# LED-Board.net
KiCad netlist of a schematic drawn in EAGLE
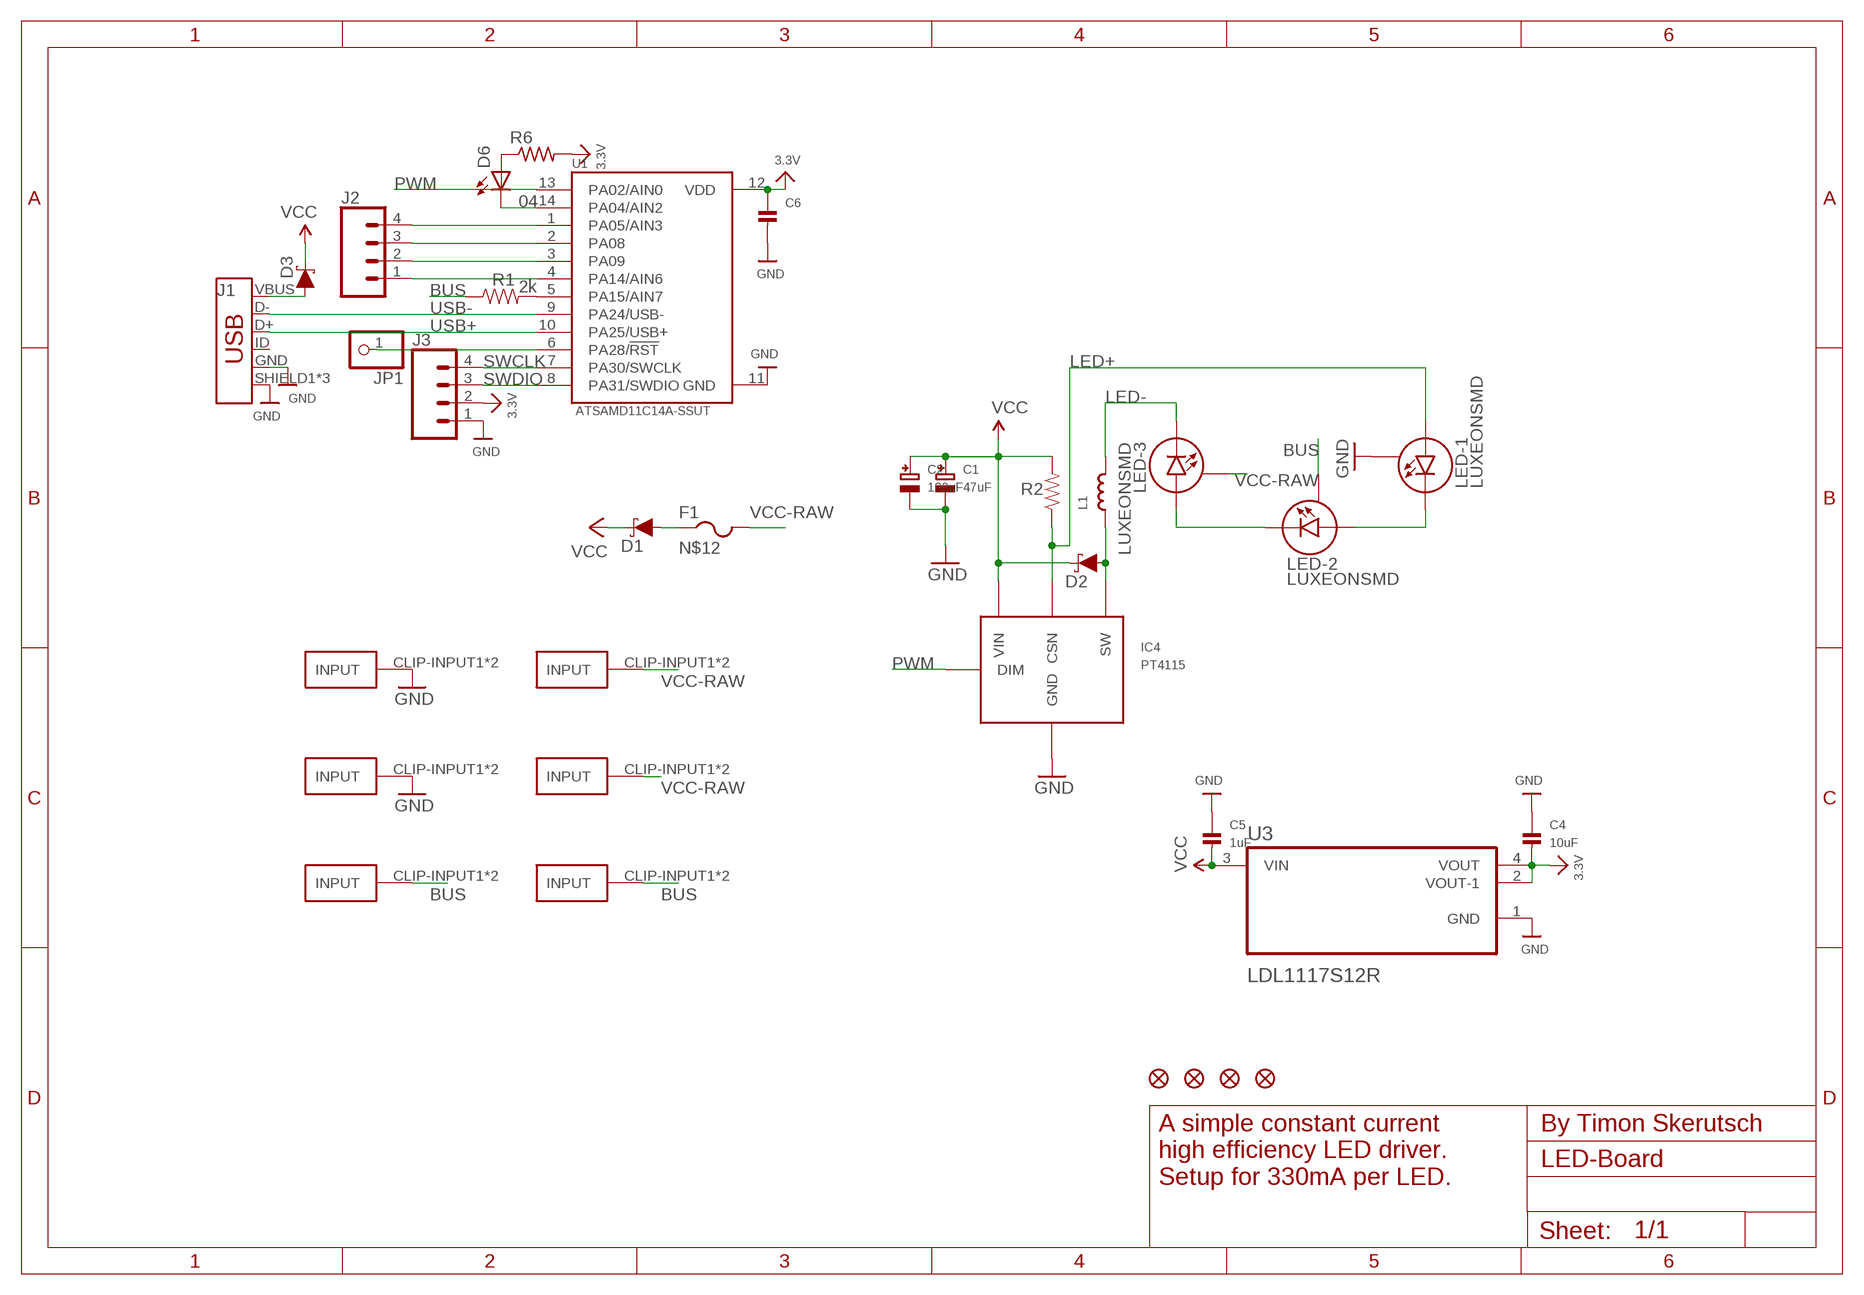
[diagram p0: schematic, sheet 1]

(export (version "E")
  (design (tool "Eeschema 10.0.6"))
  (components
    (comp (ref "C1")
      (value "47uF")
      (footprint "eagle-import:PANASONIC_C")
      (libsource (lib "eagle-import") (part "CAP_ELECTROLYTICPANASONIC_C"))
    )
    (comp (ref "C2")
      (value "100uF")
      (footprint "eagle-import:PANASONIC_C")
      (libsource (lib "eagle-import") (part "CAP_ELECTROLYTICPANASONIC_C"))
    )
    (comp (ref "C4")
      (value "10uF")
      (footprint "eagle-import:0805")
      (libsource (lib "eagle-import") (part "CAP_CERAMIC0805"))
    )
    (comp (ref "C5")
      (value "1uF")
      (footprint "eagle-import:0603")
      (libsource (lib "eagle-import") (part "CAP_CERAMIC0603"))
    )
    (comp (ref "C6")
      (value "CAP_CERAMIC0603")
      (footprint "eagle-import:0603")
      (libsource (lib "eagle-import") (part "CAP_CERAMIC0603"))
    )
    (comp (ref "D1")
      (value "3A/40V/500mV")
      (footprint "eagle-import:SMA-DIODE")
      (libsource (lib "eagle-import") (part "DIODE-SCHOTTKY-B340A"))
    )
    (comp (ref "D2")
      (value "3A/40V/500mV")
      (footprint "eagle-import:SMA-DIODE")
      (libsource (lib "eagle-import") (part "DIODE-SCHOTTKY-B340A"))
    )
    (comp (ref "D3")
      (value "3A/40V/500mV")
      (footprint "eagle-import:SMA-DIODE")
      (libsource (lib "eagle-import") (part "DIODE-SCHOTTKY-B340A"))
    )
    (comp (ref "D6")
      (value "LEDCHIPLED_0805")
      (footprint "eagle-import:CHIPLED_0805")
      (libsource (lib "eagle-import") (part "LEDCHIPLED_0805"))
    )
    (comp (ref "F1")
      (value "TLC-MSMD110/24")
      (footprint "eagle-import:1812")
      (libsource (lib "eagle-import") (part "PTCFUSE-1812"))
    )
    (comp (ref "FD1")
      (value "FIDUCIAL1X2")
      (footprint "eagle-import:FIDUCIAL-1X2")
      (libsource (lib "eagle-import") (part "FIDUCIAL1X2"))
    )
    (comp (ref "FD2")
      (value "FIDUCIAL1X2")
      (footprint "eagle-import:FIDUCIAL-1X2")
      (libsource (lib "eagle-import") (part "FIDUCIAL1X2"))
    )
    (comp (ref "FD3")
      (value "FIDUCIAL1X2")
      (footprint "eagle-import:FIDUCIAL-1X2")
      (libsource (lib "eagle-import") (part "FIDUCIAL1X2"))
    )
    (comp (ref "FD4")
      (value "FIDUCIAL1X2")
      (footprint "eagle-import:FIDUCIAL-1X2")
      (libsource (lib "eagle-import") (part "FIDUCIAL1X2"))
    )
    (comp (ref "GND-CLIP")
      (value "FUSE-HOLDER-5X20MM")
      (footprint "eagle-import:FUSE-HOLDER-5X20MM")
      (libsource (lib "eagle-import") (part "FUSE-HOLDER-5X20MM"))
    )
    (comp (ref "GND-CLIP3")
      (value "FUSE-HOLDER-5X20MM")
      (footprint "eagle-import:FUSE-HOLDER-5X20MM")
      (libsource (lib "eagle-import") (part "FUSE-HOLDER-5X20MM"))
    )
    (comp (ref "IC4")
      (value "PT4115")
      (footprint "eagle-import:PT4115")
      (libsource (lib "eagle-import") (part "PT4115"))
    )
    (comp (ref "J1")
      (value "USB_MICRO-B_FEMALE-SMT")
      (footprint "eagle-import:USB-B-MICRO-SMD")
      (libsource (lib "eagle-import") (part "USB_MICRO-B_FEMALE-SMT"))
    )
    (comp (ref "J2")
      (value "CONN_04")
      (footprint "eagle-import:1X04")
      (libsource (lib "eagle-import") (part "CONN_04"))
    )
    (comp (ref "J3")
      (value "CONN_04")
      (footprint "eagle-import:1X04")
      (libsource (lib "eagle-import") (part "CONN_04"))
    )
    (comp (ref "JP1")
      (value "PINHD-1X1")
      (footprint "eagle-import:1X01")
      (libsource (lib "eagle-import") (part "PINHD-1X1"))
    )
    (comp (ref "L1")
      (value "INDUCTORTDK_VLC6045")
      (footprint "eagle-import:INDUCTOR_6X6MM_TDK_VLC6045")
      (libsource (lib "eagle-import") (part "INDUCTORTDK_VLC6045"))
    )
    (comp (ref "LED-1")
      (value "LUXEONSMD")
      (footprint "eagle-import:LUXEON")
      (libsource (lib "eagle-import") (part "LUXEONSMD"))
    )
    (comp (ref "LED-2")
      (value "LUXEONSMD")
      (footprint "eagle-import:LUXEON")
      (libsource (lib "eagle-import") (part "LUXEONSMD"))
    )
    (comp (ref "LED-3")
      (value "LUXEONSMD")
      (footprint "eagle-import:LUXEON")
      (libsource (lib "eagle-import") (part "LUXEONSMD"))
    )
    (comp (ref "PWM-CLIP")
      (value "FUSE-HOLDER-5X20MM")
      (footprint "eagle-import:FUSE-HOLDER-5X20MM")
      (libsource (lib "eagle-import") (part "FUSE-HOLDER-5X20MM"))
    )
    (comp (ref "PWM-CLIP1")
      (value "FUSE-HOLDER-5X20MM")
      (footprint "eagle-import:FUSE-HOLDER-5X20MM")
      (libsource (lib "eagle-import") (part "FUSE-HOLDER-5X20MM"))
    )
    (comp (ref "R1")
      (value "2k")
      (footprint "eagle-import:1206")
      (libsource (lib "eagle-import") (part "RESISTOR1206"))
    )
    (comp (ref "R2")
      (value "0.3")
      (footprint "eagle-import:1206")
      (libsource (lib "eagle-import") (part "RESISTOR1206"))
    )
    (comp (ref "R6")
      (value "R-US_R0805")
      (footprint "eagle-import:R0805")
      (libsource (lib "eagle-import") (part "R-US_R0805"))
    )
    (comp (ref "U1")
      (value "ATSAMD11C14A-SSUT")
      (footprint "eagle-import:SOIC127P600X160-14N")
      (fields (field (name "MF") "Microchip"))
      (libsource (lib "eagle-import") (part "ATSAMD11C14A-SSUT"))
    )
    (comp (ref "U3")
      (value "LDL1117S12R")
      (footprint "eagle-import:SOT230P700X180-4N")
      (fields (field (name "MF") "STMicroelectronics"))
      (libsource (lib "eagle-import") (part "LDL1117S12R"))
    )
    (comp (ref "VCC-CLIP")
      (value "FUSE-HOLDER-5X20MM")
      (footprint "eagle-import:FUSE-HOLDER-5X20MM")
      (libsource (lib "eagle-import") (part "FUSE-HOLDER-5X20MM"))
    )
    (comp (ref "VCC-CLIP3")
      (value "FUSE-HOLDER-5X20MM")
      (footprint "eagle-import:FUSE-HOLDER-5X20MM")
      (libsource (lib "eagle-import") (part "FUSE-HOLDER-5X20MM"))
    )
  )
  (nets
    (net (code "1") (name "/04") (class "Default")
      (node (ref "D6") (pin "C") (pinfunction "C_C") (pintype "passive"))
      (node (ref "U1") (pin "14") (pinfunction "PA04/AIN2_14") (pintype "bidirectional"))
    )
    (net (code "2") (name "/BUS") (class "Default")
      (node (ref "LED-2") (pin "S") (pinfunction "S_S") (pintype "bidirectional"))
      (node (ref "PWM-CLIP") (pin "CLIP-INPUT1") (pinfunction "INPUT_CLIP-INPUT1") (pintype "bidirectional"))
      (node (ref "PWM-CLIP") (pin "CLIP-INPUT2") (pinfunction "INPUT_CLIP-INPUT2") (pintype "bidirectional"))
      (node (ref "PWM-CLIP1") (pin "CLIP-INPUT1") (pinfunction "INPUT_CLIP-INPUT1") (pintype "bidirectional"))
      (node (ref "PWM-CLIP1") (pin "CLIP-INPUT2") (pinfunction "INPUT_CLIP-INPUT2") (pintype "bidirectional"))
      (node (ref "R1") (pin "1") (pinfunction "1_1") (pintype "passive"))
    )
    (net (code "3") (name "/LED+") (class "Default")
      (node (ref "IC4") (pin "4") (pinfunction "CSN_4") (pintype "bidirectional"))
      (node (ref "LED-1") (pin "A") (pinfunction "A_A") (pintype "passive"))
      (node (ref "R2") (pin "1") (pinfunction "1_1") (pintype "passive"))
    )
    (net (code "4") (name "/LED-") (class "Default")
      (node (ref "L1") (pin "P$2") (pinfunction "2_P$2") (pintype "passive"))
      (node (ref "LED-3") (pin "C") (pinfunction "C_C") (pintype "passive"))
    )
    (net (code "5") (name "/N$12") (class "Default")
      (node (ref "D1") (pin "A") (pinfunction "A_A") (pintype "passive"))
      (node (ref "F1") (pin "1") (pinfunction "1_1") (pintype "passive"))
    )
    (net (code "6") (name "/PWM") (class "Default")
      (node (ref "IC4") (pin "3") (pinfunction "DIM_3") (pintype "bidirectional"))
      (node (ref "U1") (pin "13") (pinfunction "PA02/AIN0_13") (pintype "bidirectional"))
    )
    (net (code "7") (name "/SWCLK") (class "Default")
      (node (ref "J3") (pin "4") (pinfunction "4_4") (pintype "passive"))
      (node (ref "U1") (pin "7") (pinfunction "PA30/SWCLK_7") (pintype "bidirectional"))
    )
    (net (code "8") (name "/SWDIO") (class "Default")
      (node (ref "J3") (pin "3") (pinfunction "3_3") (pintype "passive"))
      (node (ref "U1") (pin "8") (pinfunction "PA31/SWDIO_8") (pintype "bidirectional"))
    )
    (net (code "9") (name "/USB+") (class "Default")
      (node (ref "J1") (pin "D+") (pinfunction "D+_D+") (pintype "bidirectional"))
      (node (ref "U1") (pin "10") (pinfunction "PA25/USB+_10") (pintype "bidirectional"))
    )
    (net (code "10") (name "/USB-") (class "Default")
      (node (ref "J1") (pin "D-") (pinfunction "D-_D-") (pintype "bidirectional"))
      (node (ref "U1") (pin "9") (pinfunction "PA24/USB-_9") (pintype "bidirectional"))
    )
    (net (code "11") (name "/VCC-RAW") (class "Default")
      (node (ref "F1") (pin "2") (pinfunction "2_2") (pintype "passive"))
      (node (ref "LED-3") (pin "S") (pinfunction "S_S") (pintype "bidirectional"))
      (node (ref "VCC-CLIP") (pin "CLIP-INPUT1") (pinfunction "INPUT_CLIP-INPUT1") (pintype "bidirectional"))
      (node (ref "VCC-CLIP") (pin "CLIP-INPUT2") (pinfunction "INPUT_CLIP-INPUT2") (pintype "bidirectional"))
      (node (ref "VCC-CLIP3") (pin "CLIP-INPUT1") (pinfunction "INPUT_CLIP-INPUT1") (pintype "bidirectional"))
      (node (ref "VCC-CLIP3") (pin "CLIP-INPUT2") (pinfunction "INPUT_CLIP-INPUT2") (pintype "bidirectional"))
    )
    (net (code "12") (name "3.3V") (class "Default")
      (node (ref "C4") (pin "2") (pinfunction "P$2_2") (pintype "passive"))
      (node (ref "C6") (pin "1") (pinfunction "P$1_1") (pintype "passive"))
      (node (ref "J3") (pin "2") (pinfunction "2_2") (pintype "passive"))
      (node (ref "R6") (pin "2") (pinfunction "2_2") (pintype "passive"))
      (node (ref "U1") (pin "12") (pinfunction "VDD_12") (pintype "power_in"))
      (node (ref "U3") (pin "2") (pinfunction "VOUT-1_2") (pintype "output"))
      (node (ref "U3") (pin "4") (pinfunction "VOUT_4") (pintype "output"))
    )
    (net (code "13") (name "GND") (class "Default")
      (node (ref "C1") (pin "-") (pinfunction "-_-") (pintype "passive"))
      (node (ref "C2") (pin "-") (pinfunction "-_-") (pintype "passive"))
      (node (ref "C4") (pin "1") (pinfunction "P$1_1") (pintype "passive"))
      (node (ref "C5") (pin "1") (pinfunction "P$1_1") (pintype "passive"))
      (node (ref "C6") (pin "2") (pinfunction "P$2_2") (pintype "passive"))
      (node (ref "GND-CLIP") (pin "CLIP-INPUT1") (pinfunction "INPUT_CLIP-INPUT1") (pintype "bidirectional"))
      (node (ref "GND-CLIP") (pin "CLIP-INPUT2") (pinfunction "INPUT_CLIP-INPUT2") (pintype "bidirectional"))
      (node (ref "GND-CLIP3") (pin "CLIP-INPUT1") (pinfunction "INPUT_CLIP-INPUT1") (pintype "bidirectional"))
      (node (ref "GND-CLIP3") (pin "CLIP-INPUT2") (pinfunction "INPUT_CLIP-INPUT2") (pintype "bidirectional"))
      (node (ref "IC4") (pin "2") (pinfunction "GND_2") (pintype "power_in"))
      (node (ref "IC4") (pin "2A") (pinfunction "GND_2A") (pintype "power_in"))
      (node (ref "J1") (pin "GND") (pinfunction "GND_GND") (pintype "power_in"))
      (node (ref "J1") (pin "SHIELD1") (pinfunction "SHIELD_SHIELD1") (pintype "bidirectional"))
      (node (ref "J1") (pin "SHIELD2") (pinfunction "SHIELD_SHIELD2") (pintype "bidirectional"))
      (node (ref "J1") (pin "SHIELD3") (pinfunction "SHIELD_SHIELD3") (pintype "bidirectional"))
      (node (ref "J3") (pin "1") (pinfunction "1_1") (pintype "passive"))
      (node (ref "LED-1") (pin "S") (pinfunction "S_S") (pintype "bidirectional"))
      (node (ref "U1") (pin "11") (pinfunction "GND_11") (pintype "power_in"))
      (node (ref "U3") (pin "1") (pinfunction "GND_1") (pintype "power_in"))
    )
    (net (code "14") (name "Net-(D3-PadA)") (class "Default")
      (node (ref "D3") (pin "A") (pinfunction "A_A") (pintype "passive"))
      (node (ref "J1") (pin "VBUS") (pinfunction "VBUS_VBUS") (pintype "power_in"))
    )
    (net (code "15") (name "Net-(D6-PadA)") (class "Default")
      (node (ref "D6") (pin "A") (pinfunction "A_A") (pintype "passive"))
      (node (ref "R6") (pin "1") (pinfunction "1_1") (pintype "passive"))
    )
    (net (code "16") (name "Net-(IC4-SW)") (class "Default")
      (node (ref "D2") (pin "A") (pinfunction "A_A") (pintype "passive"))
      (node (ref "IC4") (pin "1") (pinfunction "SW_1") (pintype "bidirectional"))
      (node (ref "L1") (pin "P$1") (pinfunction "1_P$1") (pintype "passive"))
    )
    (net (code "17") (name "Net-(LED-1-PadC)") (class "Default")
      (node (ref "LED-1") (pin "C") (pinfunction "C_C") (pintype "passive"))
      (node (ref "LED-2") (pin "A") (pinfunction "A_A") (pintype "passive"))
    )
    (net (code "18") (name "Net-(LED-2-PadC)") (class "Default")
      (node (ref "LED-2") (pin "C") (pinfunction "C_C") (pintype "passive"))
      (node (ref "LED-3") (pin "A") (pinfunction "A_A") (pintype "passive"))
    )
    (net (code "19") (name "Net-(U1-PA05{slash}AIN3)") (class "Default")
      (node (ref "J2") (pin "4") (pinfunction "4_4") (pintype "passive"))
      (node (ref "U1") (pin "1") (pinfunction "PA05/AIN3_1") (pintype "bidirectional"))
    )
    (net (code "20") (name "Net-(U1-PA08)") (class "Default")
      (node (ref "J2") (pin "3") (pinfunction "3_3") (pintype "passive"))
      (node (ref "U1") (pin "2") (pinfunction "PA08_2") (pintype "bidirectional"))
    )
    (net (code "21") (name "Net-(U1-PA09)") (class "Default")
      (node (ref "J2") (pin "2") (pinfunction "2_2") (pintype "passive"))
      (node (ref "U1") (pin "3") (pinfunction "PA09_3") (pintype "bidirectional"))
    )
    (net (code "22") (name "Net-(U1-PA14{slash}AIN6)") (class "Default")
      (node (ref "J2") (pin "1") (pinfunction "1_1") (pintype "passive"))
      (node (ref "U1") (pin "4") (pinfunction "PA14/AIN6_4") (pintype "bidirectional"))
    )
    (net (code "23") (name "Net-(U1-PA15{slash}AIN7)") (class "Default")
      (node (ref "R1") (pin "2") (pinfunction "2_2") (pintype "passive"))
      (node (ref "U1") (pin "5") (pinfunction "PA15/AIN7_5") (pintype "bidirectional"))
    )
    (net (code "24") (name "Net-(U1-PA28{slash}~{RST})") (class "Default")
      (node (ref "JP1") (pin "1") (pinfunction "1_1") (pintype "passive"))
      (node (ref "U1") (pin "6") (pinfunction "PA28/~{RST}_6") (pintype "bidirectional"))
    )
    (net (code "25") (name "VCC") (class "Default")
      (node (ref "C1") (pin "+") (pinfunction "+_+") (pintype "passive"))
      (node (ref "C2") (pin "+") (pinfunction "+_+") (pintype "passive"))
      (node (ref "C5") (pin "2") (pinfunction "P$2_2") (pintype "passive"))
      (node (ref "D1") (pin "C") (pinfunction "C_C") (pintype "passive"))
      (node (ref "D2") (pin "C") (pinfunction "C_C") (pintype "passive"))
      (node (ref "D3") (pin "C") (pinfunction "C_C") (pintype "passive"))
      (node (ref "IC4") (pin "5") (pinfunction "VIN_5") (pintype "bidirectional"))
      (node (ref "R2") (pin "2") (pinfunction "2_2") (pintype "passive"))
      (node (ref "U3") (pin "3") (pinfunction "VIN_3") (pintype "input"))
    )
    (net (code "26") (name "unconnected-(J1-PadID)") (class "Default")
      (node (ref "J1") (pin "ID") (pinfunction "ID_ID") (pintype "bidirectional"))
    )
  )
)
